# USB_A_USB_C.net
KiCad netlist of a schematic drawn in Altium Designer
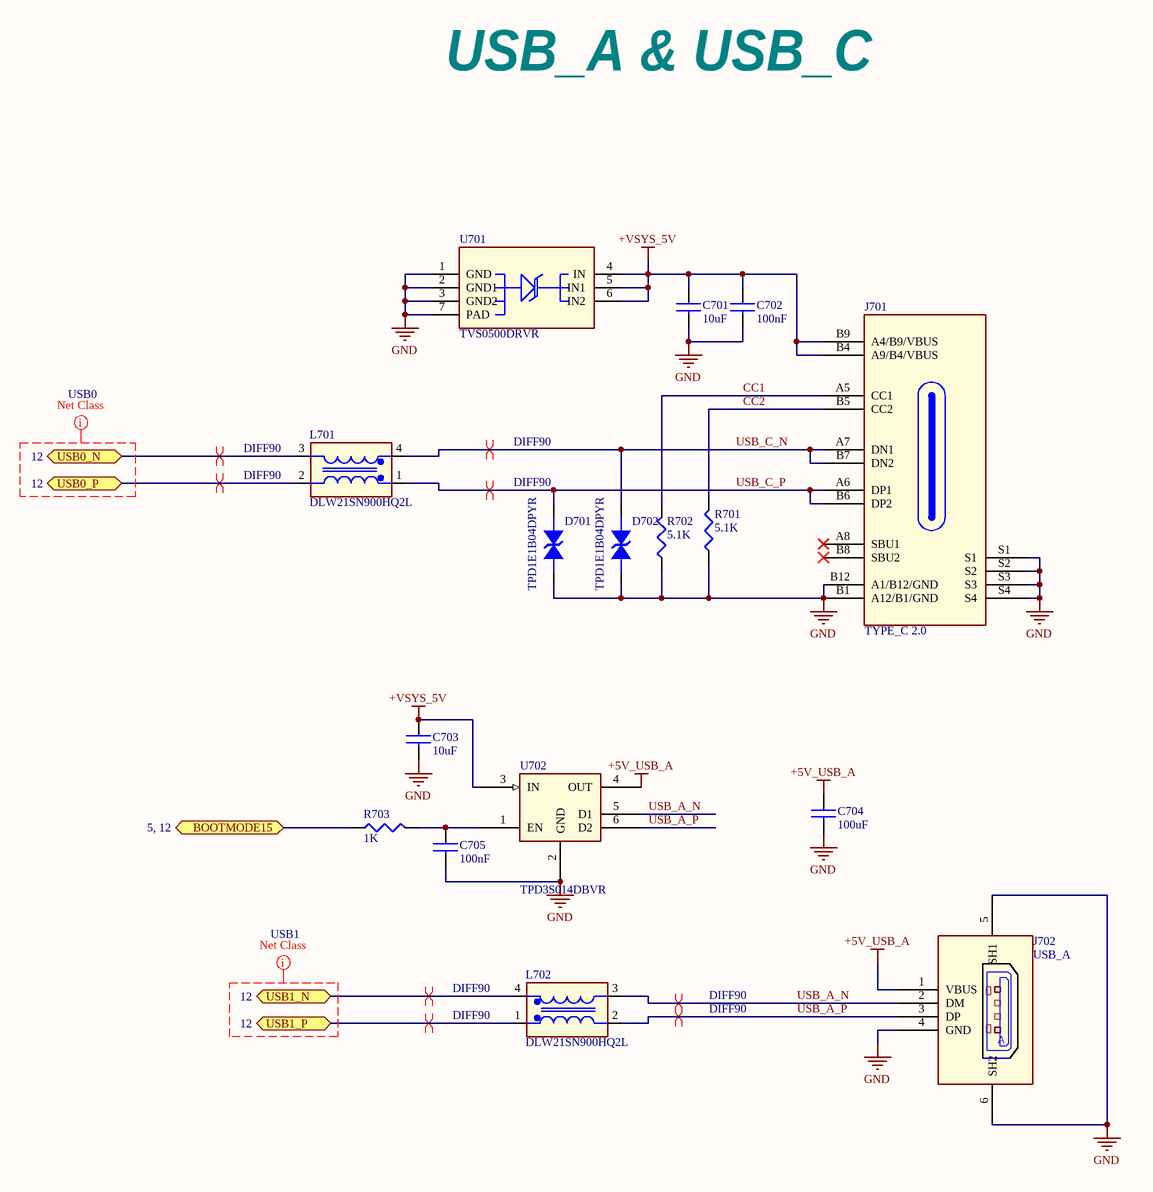
[diagram p0: USB_A & USB_C.SchDoc]

(export (version "E")
  (design (tool "Eeschema 10.0.6"))
  (components
    (comp (ref "C701")
      (value "10uF")
      (footprint "C0603")
      (description "Multilayer Ceramic Capacitor, 10 uF, 10 V, ± 10%, X5R, 0603 [1608 Metric]")
      (fields
        (field (name "MANUFACTURER") "TDK")
        (field (name "MANUFACTURER PART NUMBER") "C1608X5R1A106K080AC")
      )
      (libsource (lib "Schlib SOM AM625") (part "C1608X5R1A106K080AC"))
    )
    (comp (ref "C702")
      (value "100nF")
      (footprint "C0201")
      (description "Multilayer Ceramic Capacitor, 0.1 uF, 16 V, ± 10%, X5R, 0201 [0603 Metric]")
      (fields
        (field (name "MANUFACTURER") "Yageo")
        (field (name "MANUFACTURER PART NUMBER") "CC0201KRX5R6BB104")
      )
      (libsource (lib "Schlib SOM AM625") (part "CC0201KRX5R6BB104"))
    )
    (comp (ref "C703")
      (value "10uF")
      (footprint "C0603")
      (description "Multilayer Ceramic Capacitor, 10 uF, 10 V, ± 10%, X5R, 0603 [1608 Metric]")
      (fields
        (field (name "MANUFACTURER") "TDK")
        (field (name "MANUFACTURER PART NUMBER") "C1608X5R1A106K080AC")
      )
      (libsource (lib "Schlib SOM AM625") (part "C1608X5R1A106K080AC"))
    )
    (comp (ref "C704")
      (value "100uF")
      (footprint "C1206B/3216MM")
      (description "Multilayer Ceramic Capacitor, C Series, 100 - F, - 20%, X5R, 10 V, 1206 [3216 Metric]")
      (fields
        (field (name "MANUFACTURER") "TDK")
        (field (name "MANUFACTURER PART NUMBER") "C3216X5R1A107M160AC")
      )
      (libsource (lib "Schlib SOM AM625") (part "C3216X5R1A107M160AC"))
    )
    (comp (ref "C705")
      (value "100nF")
      (footprint "C0201")
      (description "Multilayer Ceramic Capacitor, 0.1 uF, 16 V, ± 10%, X5R, 0201 [0603 Metric]")
      (fields
        (field (name "MANUFACTURER") "Yageo")
        (field (name "MANUFACTURER PART NUMBER") "CC0201KRX5R6BB104")
      )
      (libsource (lib "Schlib SOM AM625") (part "CC0201KRX5R6BB104"))
    )
    (comp (ref "D701")
      (value "TPD1E1B04DPYR")
      (footprint "DIO_TPD1E05U06DPYR")
      (description "1-pF, ±3.6-V, ±30-kV ESD protection diode with 6-A 8/20-uS surge & Low Clamping in 0402 package")
      (fields (field (name "MANUFACTURER") "Texas Instruments"))
      (libsource (lib "Schlib SOM AM625") (part "TPD1E1B04DPYR"))
    )
    (comp (ref "D702")
      (value "TPD1E1B04DPYR")
      (footprint "DIO_TPD1E05U06DPYR")
      (description "1-pF, ±3.6-V, ±30-kV ESD protection diode with 6-A 8/20-uS surge & Low Clamping in 0402 package")
      (fields (field (name "MANUFACTURER") "Texas Instruments"))
      (libsource (lib "Schlib SOM AM625") (part "TPD1E1B04DPYR"))
    )
    (comp (ref "J701")
      (value "TYPE_C 2.0")
      (footprint "GCT_USB4105-GF-A")
      (description "Conn USB 2.0 Type C RCP 24 POS 0.3mm/0.5mm Solder RA SMD 24 Terminal 1 Port T/R")
      (fields
        (field (name "MANUFACTURER") "Global Connector Technology")
        (field (name "MANUFACTURER PART NUMBER") "USB4105-GF-A")
      )
      (libsource (lib "Schlib SOM AM625") (part "USB4105-GF-A"))
    )
    (comp (ref "J702")
      (value "USB_A")
      (footprint "GCT_USB1130-15-A_REVA")
      (description "Usb Conn, 2.0 Type A, R/a Rcpt, 4Pos, Th Rohs Compliant: Yes")
      (fields
        (field (name "MANUFACTURER") "Global Connector Technology")
        (field (name "MANUFACTURER PART NUMBER") "USB1130-15-A")
      )
      (libsource (lib "Schlib SOM AM625") (part "USB1130-15-A"))
    )
    (comp (ref "L701")
      (value "DLW21SN900HQ2L")
      (footprint "IND_DLW21S_0805_MUR")
      (description "Ind Common Mode Choke Wirewound 90Ohm 25% 100MHz 280mA 0805 Embossed T/R")
      (fields (field (name "MANUFACTURER") "Murata") (field (name "TOLERANCE") "25%"))
      (libsource (lib "") (part "DLW21SN900HQ2L_1"))
    )
    (comp (ref "L702")
      (value "DLW21SN900HQ2L")
      (footprint "IND_DLW21S_0805_MUR")
      (description "Ind Common Mode Choke Wirewound 90Ohm 25% 100MHz 280mA 0805 Embossed T/R")
      (fields (field (name "MANUFACTURER") "Murata") (field (name "TOLERANCE") "25%"))
      (libsource (lib "Schlib SOM AM625") (part "DLW21SN900HQ2L"))
    )
    (comp (ref "R701")
      (value "5.1K")
      (footprint "R0402")
      (description "SMD Chip Resistor, 5.1 kOhm, ± 1%, 63 mW, 0402 [1005 Metric], Thick Film, General Purpose")
      (fields
        (field (name "MANUFACTURER") "Yageo")
        (field (name "MANUFACTURER PART NUMBER") "AC0402FR-075K1L")
      )
      (libsource (lib "Schlib SOM AM625") (part "AC0402FR-075K1L"))
    )
    (comp (ref "R702")
      (value "5.1K")
      (footprint "R0402")
      (description "SMD Chip Resistor, 5.1 kOhm, ± 1%, 63 mW, 0402 [1005 Metric], Thick Film, General Purpose")
      (fields
        (field (name "MANUFACTURER") "Yageo")
        (field (name "MANUFACTURER PART NUMBER") "AC0402FR-075K1L")
      )
      (libsource (lib "Schlib SOM AM625") (part "AC0402FR-075K1L"))
    )
    (comp (ref "R703")
      (value "1K")
      (footprint "R0402")
      (description "SMD Chip Resistor, 1 kOhm, ± 1%, 63 mW, 0402 [1005 Metric], Thick Film, General Purpose")
      (fields
        (field (name "MANUFACTURER") "Yageo")
        (field (name "MANUFACTURER PART NUMBER") "RC0402FR-071KL")
      )
      (libsource (lib "Schlib SOM AM625") (part "RC0402FR-071KL"))
    )
    (comp (ref "U701")
      (value "TVS0500DRVR")
      (footprint "wson6_0d65_2x2x0_8mm")
      (description "Diode TVS Single Uni-Dir 5V 400W 6-Pin WSON EP T/R")
      (fields (field (name "MANUFACTURER") "Texas Instruments"))
      (libsource (lib "Schlib SOM AM625") (part "TVS0500DRVR"))
    )
    (comp (ref "U702")
      (value "TPD3S014DBVR")
      (footprint "SOT23-6")
      (description "Current-limit switch and D+/D– ESD protection for USB Host ports 6-SOT-23 -40 to 85")
      (fields (field (name "MANUFACTURER") "Texas Instruments"))
      (libsource (lib "Schlib SOM AM625") (part "TPD3S014DBVR"))
    )
  )
  (nets
    (net (code "1") (name "+5V_USB_A") (class "Default")
      (node (ref "C704") (pin "1") (pinfunction "1_1") (pintype "passive"))
      (node (ref "J702") (pin "1") (pinfunction "VBUS_1") (pintype "passive"))
      (node (ref "U702") (pin "4") (pinfunction "OUT_4") (pintype "passive"))
    )
    (net (code "2") (name "+VSYS_5V") (class "Default")
      (node (ref "C701") (pin "1") (pinfunction "1_1") (pintype "passive"))
      (node (ref "C702") (pin "1") (pinfunction "1_1") (pintype "passive"))
      (node (ref "C703") (pin "1") (pinfunction "1_1") (pintype "passive"))
      (node (ref "J701") (pin "B4") (pinfunction "A9/B4/VBUS_B4") (pintype "passive"))
      (node (ref "J701") (pin "B9") (pinfunction "A4/B9/VBUS_B9") (pintype "passive"))
      (node (ref "U701") (pin "4") (pinfunction "IN_4") (pintype "passive"))
      (node (ref "U701") (pin "5") (pinfunction "IN1_5") (pintype "passive"))
      (node (ref "U701") (pin "6") (pinfunction "IN2_6") (pintype "passive"))
      (node (ref "U702") (pin "3") (pinfunction "IN_3") (pintype "input"))
    )
    (net (code "3") (name "/BOOTMODE15") (class "Default")
      (node (ref "R703") (pin "1") (pinfunction "1_1") (pintype "passive"))
    )
    (net (code "4") (name "/CC1") (class "Default")
      (node (ref "J701") (pin "A5") (pinfunction "CC1_A5") (pintype "passive"))
      (node (ref "R702") (pin "2") (pinfunction "2_2") (pintype "passive"))
    )
    (net (code "5") (name "/CC2") (class "Default")
      (node (ref "J701") (pin "B5") (pinfunction "CC2_B5") (pintype "passive"))
      (node (ref "R701") (pin "2") (pinfunction "2_2") (pintype "passive"))
    )
    (net (code "6") (name "/USB0_N") (class "Default")
      (node (ref "L701") (pin "3") (pinfunction "3_3") (pintype "passive"))
    )
    (net (code "7") (name "/USB0_P") (class "Default")
      (node (ref "L701") (pin "2") (pinfunction "2_2") (pintype "passive"))
    )
    (net (code "8") (name "/USB1_N") (class "Default")
      (node (ref "L702") (pin "4") (pinfunction "4_4") (pintype "passive"))
    )
    (net (code "9") (name "/USB1_P") (class "Default")
      (node (ref "L702") (pin "1") (pinfunction "1_1") (pintype "passive"))
    )
    (net (code "10") (name "/USB_A_N") (class "Default")
      (node (ref "J702") (pin "2") (pinfunction "DM_2") (pintype "passive"))
      (node (ref "L702") (pin "3") (pinfunction "3_3") (pintype "passive"))
      (node (ref "U702") (pin "5") (pinfunction "D1_5") (pintype "passive"))
    )
    (net (code "11") (name "/USB_A_P") (class "Default")
      (node (ref "J702") (pin "3") (pinfunction "DP_3") (pintype "passive"))
      (node (ref "L702") (pin "2") (pinfunction "2_2") (pintype "passive"))
      (node (ref "U702") (pin "6") (pinfunction "D2_6") (pintype "passive"))
    )
    (net (code "12") (name "/USB_C_N") (class "Default")
      (node (ref "D702") (pin "2") (pinfunction "2_2") (pintype "passive"))
      (node (ref "J701") (pin "A7") (pinfunction "DN1_A7") (pintype "passive"))
      (node (ref "J701") (pin "B7") (pinfunction "DN2_B7") (pintype "passive"))
      (node (ref "L701") (pin "4") (pinfunction "4_4") (pintype "passive"))
    )
    (net (code "13") (name "/USB_C_P") (class "Default")
      (node (ref "D701") (pin "2") (pinfunction "2_2") (pintype "passive"))
      (node (ref "J701") (pin "A6") (pinfunction "DP1_A6") (pintype "passive"))
      (node (ref "J701") (pin "B6") (pinfunction "DP2_B6") (pintype "passive"))
      (node (ref "L701") (pin "1") (pinfunction "1_1") (pintype "passive"))
    )
    (net (code "14") (name "GND") (class "Default")
      (node (ref "C701") (pin "2") (pinfunction "2_2") (pintype "passive"))
      (node (ref "C702") (pin "2") (pinfunction "2_2") (pintype "passive"))
      (node (ref "C703") (pin "2") (pinfunction "2_2") (pintype "passive"))
      (node (ref "C704") (pin "2") (pinfunction "2_2") (pintype "passive"))
      (node (ref "C705") (pin "2") (pinfunction "2_2") (pintype "passive"))
      (node (ref "D701") (pin "1") (pinfunction "1_1") (pintype "passive"))
      (node (ref "D702") (pin "1") (pinfunction "1_1") (pintype "passive"))
      (node (ref "J701") (pin "B1") (pinfunction "A12/B1/GND_B1") (pintype "passive"))
      (node (ref "J701") (pin "B12") (pinfunction "A1/B12/GND_B12") (pintype "passive"))
      (node (ref "J701") (pin "S1") (pinfunction "S1_S1") (pintype "passive"))
      (node (ref "J701") (pin "S2") (pinfunction "S2_S2") (pintype "passive"))
      (node (ref "J701") (pin "S3") (pinfunction "S3_S3") (pintype "passive"))
      (node (ref "J701") (pin "S4") (pinfunction "S4_S4") (pintype "passive"))
      (node (ref "J702") (pin "4") (pinfunction "GND_4") (pintype "passive"))
      (node (ref "J702") (pin "5") (pinfunction "SH1_5") (pintype "passive"))
      (node (ref "J702") (pin "6") (pinfunction "SH2_6") (pintype "passive"))
      (node (ref "R701") (pin "1") (pinfunction "1_1") (pintype "passive"))
      (node (ref "R702") (pin "1") (pinfunction "1_1") (pintype "passive"))
      (node (ref "U701") (pin "1") (pinfunction "GND_1") (pintype "passive"))
      (node (ref "U701") (pin "2") (pinfunction "GND1_2") (pintype "passive"))
      (node (ref "U701") (pin "3") (pinfunction "GND2_3") (pintype "passive"))
      (node (ref "U701") (pin "7") (pinfunction "PAD_7") (pintype "passive"))
      (node (ref "U702") (pin "2") (pinfunction "GND_2") (pintype "power_in"))
    )
    (net (code "15") (name "Net-(U702-EN)") (class "Default")
      (node (ref "C705") (pin "1") (pinfunction "1_1") (pintype "passive"))
      (node (ref "R703") (pin "2") (pinfunction "2_2") (pintype "passive"))
      (node (ref "U702") (pin "1") (pinfunction "EN_1") (pintype "passive"))
    )
    (net (code "16") (name "unconnected-(J701-SBU1-PadA8)") (class "Default")
      (node (ref "J701") (pin "A8") (pinfunction "SBU1_A8") (pintype "passive+no_connect"))
    )
    (net (code "17") (name "unconnected-(J701-SBU2-PadB8)") (class "Default")
      (node (ref "J701") (pin "B8") (pinfunction "SBU2_B8") (pintype "passive+no_connect"))
    )
  )
)
